# CZ201E_V2_0.net
KiCad netlist of a schematic drawn in Altium Designer
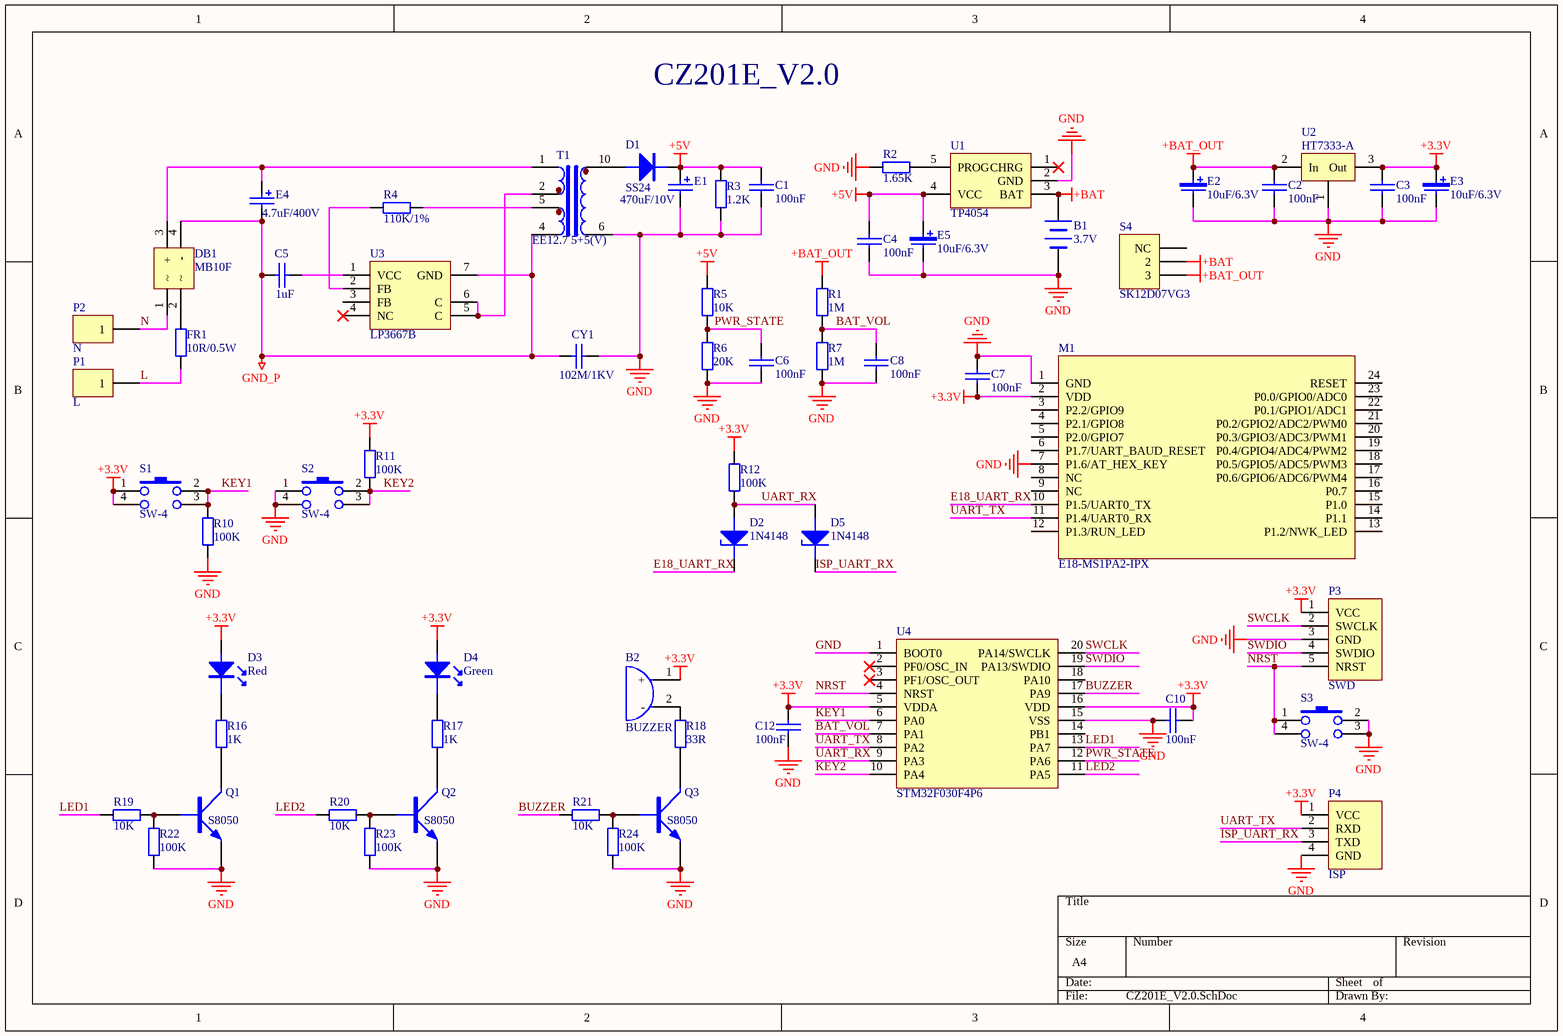
[diagram p0: CZ201E_V2.0.SchDoc]

(export (version "E")
  (design (tool "Eeschema 10.0.6"))
  (components
    (comp (ref "B1")
      (value "3.7V")
      (footprint "Cheng_Interface Unit:XH2.54-2P-BAT")
      (libsource (lib "Cheng_Misc Component") (part "BATTERY"))
    )
    (comp (ref "B2")
      (value "BUZZER")
      (footprint "Cheng_Misc Component:BEEZ")
      (libsource (lib "Cheng_Misc Component") (part "BUZZER"))
    )
    (comp (ref "C1")
      (value "100nF")
      (footprint "Cheng_Resistor_Capacitor:0603_CN")
      (libsource (lib "Cheng_Resistor_Capacitor") (part "Cap1"))
    )
    (comp (ref "C2")
      (value "100nF")
      (footprint "Cheng_Resistor_Capacitor:0603_CN")
      (libsource (lib "Cheng_Resistor_Capacitor") (part "Cap1"))
    )
    (comp (ref "C3")
      (value "100nF")
      (footprint "Cheng_Resistor_Capacitor:0603_CN")
      (libsource (lib "Cheng_Resistor_Capacitor") (part "Cap1"))
    )
    (comp (ref "C4")
      (value "100nF")
      (footprint "Cheng_Resistor_Capacitor:0603_CN")
      (libsource (lib "Cheng_Resistor_Capacitor") (part "Cap1"))
    )
    (comp (ref "C5")
      (value "1uF")
      (footprint "Cheng_Resistor_Capacitor:0603_CN")
      (libsource (lib "Cheng_Resistor_Capacitor") (part "Cap1"))
    )
    (comp (ref "C6")
      (value "100nF")
      (footprint "Cheng_Resistor_Capacitor:0603_CN")
      (libsource (lib "Cheng_Resistor_Capacitor") (part "Cap1"))
    )
    (comp (ref "C7")
      (value "100nF")
      (footprint "Cheng_Resistor_Capacitor:0603_CN")
      (libsource (lib "Cheng_Resistor_Capacitor") (part "Cap1"))
    )
    (comp (ref "C8")
      (value "100nF")
      (footprint "Cheng_Resistor_Capacitor:0603_CN")
      (libsource (lib "Cheng_Resistor_Capacitor") (part "Cap1"))
    )
    (comp (ref "C10")
      (value "100nF")
      (footprint "Cheng_Resistor_Capacitor:0603_CN")
      (libsource (lib "Cheng_Resistor_Capacitor") (part "Cap1"))
    )
    (comp (ref "C12")
      (value "100nF")
      (footprint "Cheng_Resistor_Capacitor:0603_CN")
      (libsource (lib "Cheng_Resistor_Capacitor") (part "Cap1"))
    )
    (comp (ref "CY1")
      (value "102M/1KV")
      (footprint "Cheng_Resistor_Capacitor:CY-5MM")
      (libsource (lib "Cheng_Resistor_Capacitor") (part "Cap1"))
    )
    (comp (ref "D1")
      (value "SS24")
      (footprint "Cheng_Diode_Transistor:DO-214AC(SMA)")
      (description "SS14,SS24,SS34,M7")
      (libsource (lib "Cheng_Diode_Transistor") (part "Diode-A"))
    )
    (comp (ref "D2")
      (value "1N4148")
      (footprint "Cheng_Diode_Transistor:LL-34")
      (libsource (lib "Cheng_Diode_Transistor") (part "Diode-B"))
    )
    (comp (ref "D3")
      (value "Red")
      (footprint "Cheng_Diode_Transistor:0603_LED")
      (libsource (lib "Cheng_Diode_Transistor") (part "LED"))
    )
    (comp (ref "D4")
      (value "Green")
      (footprint "Cheng_Diode_Transistor:0603_LED")
      (libsource (lib "Cheng_Diode_Transistor") (part "LED"))
    )
    (comp (ref "D5")
      (value "1N4148")
      (footprint "Cheng_Diode_Transistor:LL-34")
      (libsource (lib "Cheng_Diode_Transistor") (part "Diode-B"))
    )
    (comp (ref "DB1")
      (value "MB10F")
      (footprint "Cheng_Diode_Transistor:MB10F")
      (libsource (lib "Cheng_Diode_Transistor") (part "MB10F"))
    )
    (comp (ref "E1")
      (value "470uF/10V")
      (footprint "Cheng_Resistor_Capacitor:CS_470uF/16V")
      (libsource (lib "Cheng_Resistor_Capacitor") (part "Cap Pol1"))
    )
    (comp (ref "E2")
      (value "10uF/6.3V")
      (footprint "Cheng_Resistor_Capacitor:3216_E")
      (libsource (lib "Cheng_Resistor_Capacitor") (part "Cap Ta"))
    )
    (comp (ref "E3")
      (value "10uF/6.3V")
      (footprint "Cheng_Resistor_Capacitor:3216_E")
      (libsource (lib "Cheng_Resistor_Capacitor") (part "Cap Ta"))
    )
    (comp (ref "E4")
      (value "4.7uF/400V")
      (footprint "Cheng_Resistor_Capacitor:CS_220uF/25V")
      (libsource (lib "Cheng_Resistor_Capacitor") (part "Cap Pol1"))
    )
    (comp (ref "E5")
      (value "10uF/6.3V")
      (footprint "Cheng_Resistor_Capacitor:3216_E")
      (libsource (lib "Cheng_Resistor_Capacitor") (part "Cap Ta"))
    )
    (comp (ref "FR1")
      (value "10R/0.5W")
      (footprint "Cheng_Resistor_Capacitor:R0.12L")
      (libsource (lib "") (part "Res1_1"))
    )
    (comp (ref "M1")
      (value "E18-MS1PA2-IPX")
      (footprint "Cheng_Module:E18-MS1PA2-IPX")
      (libsource (lib "Cheng_Module") (part "E18-MS1PA2-IPX"))
    )
    (comp (ref "P1")
      (value "L")
      (footprint "Cheng_Interface Unit:CP3M-6*5*8.5MM")
      (description "Header, 1-Pin")
      (fields (field (name "PUBLISHER") "Altium Limited"))
      (libsource (lib "Cheng_Interface Unit") (part "Header 1"))
    )
    (comp (ref "P2")
      (value "N")
      (footprint "Cheng_Interface Unit:CP3M-6*5*8.5MM")
      (description "Header, 1-Pin")
      (fields (field (name "PUBLISHER") "Altium Limited"))
      (libsource (lib "Cheng_Interface Unit") (part "Header 1"))
    )
    (comp (ref "P3")
      (value "SWD")
      (footprint "Cheng_Interface Unit:XH2.54-5P")
      (libsource (lib "Cheng_Interface Unit") (part "SWD"))
    )
    (comp (ref "P4")
      (value "ISP")
      (footprint "Cheng_Interface Unit:XH2.54-4P")
      (libsource (lib "Cheng_Interface Unit") (part "ISP_UART"))
    )
    (comp (ref "Q1")
      (value "S8050")
      (footprint "Cheng_Diode_Transistor:SOT-23")
      (libsource (lib "Cheng_Diode_Transistor") (part "8050"))
    )
    (comp (ref "Q2")
      (value "S8050")
      (footprint "Cheng_Diode_Transistor:SOT-23")
      (libsource (lib "Cheng_Diode_Transistor") (part "8050"))
    )
    (comp (ref "Q3")
      (value "S8050")
      (footprint "Cheng_Diode_Transistor:SOT-23")
      (libsource (lib "Cheng_Diode_Transistor") (part "8050"))
    )
    (comp (ref "R1")
      (value "1M")
      (footprint "Cheng_Resistor_Capacitor:0603_RN")
      (libsource (lib "") (part "Res1_1"))
    )
    (comp (ref "R2")
      (value "1.65K")
      (footprint "Cheng_Resistor_Capacitor:0603_RN")
      (libsource (lib "") (part "Res1_2"))
    )
    (comp (ref "R3")
      (value "1.2K")
      (footprint "Cheng_Resistor_Capacitor:0603_RN")
      (libsource (lib "") (part "Res1_1"))
    )
    (comp (ref "R4")
      (value "110K/1%")
      (footprint "Cheng_Resistor_Capacitor:0603_RN")
      (libsource (lib "") (part "Res1_2"))
    )
    (comp (ref "R5")
      (value "10K")
      (footprint "Cheng_Resistor_Capacitor:0603_RN")
      (libsource (lib "") (part "Res1_1"))
    )
    (comp (ref "R6")
      (value "20K")
      (footprint "Cheng_Resistor_Capacitor:0603_RN")
      (libsource (lib "") (part "Res1_1"))
    )
    (comp (ref "R7")
      (value "1M")
      (footprint "Cheng_Resistor_Capacitor:0603_RN")
      (libsource (lib "") (part "Res1_1"))
    )
    (comp (ref "R10")
      (value "100K")
      (footprint "Cheng_Resistor_Capacitor:0603_RN")
      (libsource (lib "") (part "Res1_1"))
    )
    (comp (ref "R11")
      (value "100K")
      (footprint "Cheng_Resistor_Capacitor:0603_RN")
      (libsource (lib "") (part "Res1_1"))
    )
    (comp (ref "R12")
      (value "100K")
      (footprint "Cheng_Resistor_Capacitor:0603_RN")
      (libsource (lib "") (part "Res1_1"))
    )
    (comp (ref "R16")
      (value "1K")
      (footprint "Cheng_Resistor_Capacitor:0603_RN")
      (libsource (lib "") (part "Res1_1"))
    )
    (comp (ref "R17")
      (value "1K")
      (footprint "Cheng_Resistor_Capacitor:0603_RN")
      (libsource (lib "") (part "Res1_1"))
    )
    (comp (ref "R18")
      (value "33R")
      (footprint "Cheng_Resistor_Capacitor:0603_RN")
      (libsource (lib "") (part "Res1_1"))
    )
    (comp (ref "R19")
      (value "10K")
      (footprint "Cheng_Resistor_Capacitor:0603_RN")
      (libsource (lib "Cheng_Resistor_Capacitor") (part "Res1"))
    )
    (comp (ref "R20")
      (value "10K")
      (footprint "Cheng_Resistor_Capacitor:0603_RN")
      (libsource (lib "Cheng_Resistor_Capacitor") (part "Res1"))
    )
    (comp (ref "R21")
      (value "10K")
      (footprint "Cheng_Resistor_Capacitor:0603_RN")
      (libsource (lib "Cheng_Resistor_Capacitor") (part "Res1"))
    )
    (comp (ref "R22")
      (value "100K")
      (footprint "Cheng_Resistor_Capacitor:0603_RN")
      (libsource (lib "") (part "Res1_1"))
    )
    (comp (ref "R23")
      (value "100K")
      (footprint "Cheng_Resistor_Capacitor:0603_RN")
      (libsource (lib "") (part "Res1_1"))
    )
    (comp (ref "R24")
      (value "100K")
      (footprint "Cheng_Resistor_Capacitor:0603_RN")
      (libsource (lib "") (part "Res1_1"))
    )
    (comp (ref "S1")
      (value "SW-4")
      (footprint "Cheng_Misc Component:KEY-6*6MM-DIP")
      (libsource (lib "Cheng_Misc Component") (part "SW-4"))
    )
    (comp (ref "S2")
      (value "SW-4")
      (footprint "Cheng_Misc Component:KEY-6*6MM-DIP")
      (libsource (lib "Cheng_Misc Component") (part "SW-4"))
    )
    (comp (ref "S3")
      (value "SW-4")
      (footprint "Cheng_Misc Component:KEY-4*4*1.5MM-SMD")
      (libsource (lib "Cheng_Misc Component") (part "SW-4"))
    )
    (comp (ref "S4")
      (value "SK12D07VG3")
      (footprint "Cheng_Misc Component:SK12D07VG3")
      (libsource (lib "Cheng_Misc Component") (part "SK12D07VG3"))
    )
    (comp (ref "T1")
      (value "EE12.7 5+5(V)")
      (footprint "EE12.7 5+5(V)")
      (libsource (lib "CZ201E_V2.0") (part "EE12.7 5+5(V)"))
    )
    (comp (ref "U1")
      (value "TP4054")
      (footprint "Cheng_Diode_Transistor:SOT-23-5")
      (description "TP4054,LTC4054 ,PJ4054MR")
      (libsource (lib "Cheng_IC") (part "QX4054"))
    )
    (comp (ref "U2")
      (value "HT7333-A")
      (footprint "SOT-89")
      (description "HT7533; Output 500mA; Iq: 5uA, max= 7uA")
      (libsource (lib "Cheng_Manostat") (part "HT7833"))
    )
    (comp (ref "U3")
      (value "LP3667B")
      (footprint "Cheng_Manostat:SOP7")
      (description "LP3667A, LP3667B, LP3667AH, LP3667BH")
      (libsource (lib "Cheng_Manostat") (part "LP3667B"))
    )
    (comp (ref "U4")
      (value "STM32F030F4P6")
      (footprint "Cheng_IC:TSSOP20")
      (libsource (lib "Cheng_STM32") (part "STM32F030F4P6"))
    )
  )
  (nets
    (net (code "1") (name "+3.3V") (class "Default")
      (node (ref "B2") (pin "1") (pinfunction "+_1") (pintype "passive"))
      (node (ref "C10") (pin "1") (pinfunction "1_1") (pintype "passive"))
      (node (ref "C12") (pin "1") (pinfunction "1_1") (pintype "passive"))
      (node (ref "C3") (pin "1") (pinfunction "1_1") (pintype "passive"))
      (node (ref "C7") (pin "2") (pinfunction "2_2") (pintype "passive"))
      (node (ref "D3") (pin "A") (pinfunction "1_A") (pintype "passive"))
      (node (ref "D4") (pin "A") (pinfunction "1_A") (pintype "passive"))
      (node (ref "E3") (pin "1") (pinfunction "1_1") (pintype "passive"))
      (node (ref "M1") (pin "2") (pinfunction "VDD_2") (pintype "passive"))
      (node (ref "P3") (pin "1") (pinfunction "VCC_1") (pintype "passive"))
      (node (ref "P4") (pin "1") (pinfunction "VCC_1") (pintype "passive"))
      (node (ref "R11") (pin "2") (pinfunction "2_2") (pintype "passive"))
      (node (ref "R12") (pin "2") (pinfunction "2_2") (pintype "passive"))
      (node (ref "S1") (pin "1") (pinfunction "1_1") (pintype "passive"))
      (node (ref "S1") (pin "4") (pinfunction "4_4") (pintype "passive"))
      (node (ref "U2") (pin "3") (pinfunction "Out_3") (pintype "passive"))
      (node (ref "U4") (pin "16") (pinfunction "VDD_16") (pintype "passive"))
      (node (ref "U4") (pin "5") (pinfunction "VDDA_5") (pintype "passive"))
    )
    (net (code "2") (name "+5V") (class "Default")
      (node (ref "C1") (pin "1") (pinfunction "1_1") (pintype "passive"))
      (node (ref "C4") (pin "1") (pinfunction "1_1") (pintype "passive"))
      (node (ref "D1") (pin "K") (pinfunction "2_K") (pintype "passive"))
      (node (ref "E1") (pin "1") (pinfunction "1_1") (pintype "passive"))
      (node (ref "E5") (pin "1") (pinfunction "1_1") (pintype "passive"))
      (node (ref "R3") (pin "2") (pinfunction "2_2") (pintype "passive"))
      (node (ref "R5") (pin "2") (pinfunction "2_2") (pintype "passive"))
      (node (ref "U1") (pin "4") (pinfunction "VCC_4") (pintype "power_in"))
    )
    (net (code "3") (name "+BAT") (class "Default")
      (node (ref "B1") (pin "1") (pinfunction "+_1") (pintype "passive"))
      (node (ref "S4") (pin "2") (pinfunction "2_2") (pintype "passive"))
      (node (ref "U1") (pin "3") (pinfunction "BAT_3") (pintype "passive"))
    )
    (net (code "4") (name "+BAT_OUT") (class "Default")
      (node (ref "C2") (pin "1") (pinfunction "1_1") (pintype "passive"))
      (node (ref "E2") (pin "1") (pinfunction "1_1") (pintype "passive"))
      (node (ref "R1") (pin "2") (pinfunction "2_2") (pintype "passive"))
      (node (ref "S4") (pin "3") (pinfunction "3_3") (pintype "passive"))
      (node (ref "U2") (pin "2") (pinfunction "In_2") (pintype "passive"))
    )
    (net (code "5") (name "/BAT_VOL") (class "Default")
      (node (ref "C8") (pin "1") (pinfunction "1_1") (pintype "passive"))
      (node (ref "R1") (pin "1") (pinfunction "1_1") (pintype "passive"))
      (node (ref "R7") (pin "2") (pinfunction "2_2") (pintype "passive"))
      (node (ref "U4") (pin "7") (pinfunction "PA1_7") (pintype "passive"))
    )
    (net (code "6") (name "/BUZZER") (class "Default")
      (node (ref "R21") (pin "2") (pinfunction "2_2") (pintype "passive"))
      (node (ref "U4") (pin "17") (pinfunction "PA9_17") (pintype "passive"))
    )
    (net (code "7") (name "/E18_UART_RX") (class "Default")
      (node (ref "D2") (pin "K") (pinfunction "2_K") (pintype "passive"))
      (node (ref "M1") (pin "10") (pinfunction "P1.5/UART0_TX_10") (pintype "passive"))
    )
    (net (code "8") (name "/ISP_UART_RX") (class "Default")
      (node (ref "D5") (pin "K") (pinfunction "2_K") (pintype "passive"))
      (node (ref "P4") (pin "3") (pinfunction "TXD_3") (pintype "passive"))
    )
    (net (code "9") (name "/KEY1") (class "Default")
      (node (ref "R10") (pin "2") (pinfunction "2_2") (pintype "passive"))
      (node (ref "S1") (pin "2") (pinfunction "2_2") (pintype "passive"))
      (node (ref "S1") (pin "3") (pinfunction "3_3") (pintype "passive"))
      (node (ref "U4") (pin "6") (pinfunction "PA0_6") (pintype "passive"))
    )
    (net (code "10") (name "/KEY2") (class "Default")
      (node (ref "R11") (pin "1") (pinfunction "1_1") (pintype "passive"))
      (node (ref "S2") (pin "2") (pinfunction "2_2") (pintype "passive"))
      (node (ref "S2") (pin "3") (pinfunction "3_3") (pintype "passive"))
      (node (ref "U4") (pin "10") (pinfunction "PA4_10") (pintype "passive"))
    )
    (net (code "11") (name "/L") (class "Default")
      (node (ref "FR1") (pin "1") (pinfunction "1_1") (pintype "passive"))
      (node (ref "P1") (pin "1") (pinfunction "1_1") (pintype "passive"))
    )
    (net (code "12") (name "/LED1") (class "Default")
      (node (ref "R19") (pin "2") (pinfunction "2_2") (pintype "passive"))
      (node (ref "U4") (pin "13") (pinfunction "PA7_13") (pintype "passive"))
    )
    (net (code "13") (name "/LED2") (class "Default")
      (node (ref "R20") (pin "2") (pinfunction "2_2") (pintype "passive"))
      (node (ref "U4") (pin "11") (pinfunction "PA5_11") (pintype "passive"))
    )
    (net (code "14") (name "/N") (class "Default")
      (node (ref "DB1") (pin "1") (pinfunction "~_1") (pintype "passive"))
      (node (ref "P2") (pin "1") (pinfunction "1_1") (pintype "passive"))
    )
    (net (code "15") (name "/NRST") (class "Default")
      (node (ref "P3") (pin "5") (pinfunction "NRST_5") (pintype "passive"))
      (node (ref "S3") (pin "1") (pinfunction "1_1") (pintype "passive"))
      (node (ref "S3") (pin "4") (pinfunction "4_4") (pintype "passive"))
      (node (ref "U4") (pin "4") (pinfunction "NRST_4") (pintype "passive"))
    )
    (net (code "16") (name "/PWR_STATE") (class "Default")
      (node (ref "C6") (pin "1") (pinfunction "1_1") (pintype "passive"))
      (node (ref "R5") (pin "1") (pinfunction "1_1") (pintype "passive"))
      (node (ref "R6") (pin "2") (pinfunction "2_2") (pintype "passive"))
      (node (ref "U4") (pin "12") (pinfunction "PA6_12") (pintype "passive"))
    )
    (net (code "17") (name "/SWCLK") (class "Default")
      (node (ref "P3") (pin "2") (pinfunction "SWCLK_2") (pintype "passive"))
      (node (ref "U4") (pin "20") (pinfunction "PA14/SWCLK_20") (pintype "passive"))
    )
    (net (code "18") (name "/SWDIO") (class "Default")
      (node (ref "P3") (pin "4") (pinfunction "SWDIO_4") (pintype "passive"))
      (node (ref "U4") (pin "19") (pinfunction "PA13/SWDIO_19") (pintype "passive"))
    )
    (net (code "19") (name "/UART_RX") (class "Default")
      (node (ref "D2") (pin "A") (pinfunction "1_A") (pintype "passive"))
      (node (ref "D5") (pin "A") (pinfunction "1_A") (pintype "passive"))
      (node (ref "R12") (pin "1") (pinfunction "1_1") (pintype "passive"))
      (node (ref "U4") (pin "9") (pinfunction "PA3_9") (pintype "passive"))
    )
    (net (code "20") (name "/UART_TX") (class "Default")
      (node (ref "M1") (pin "11") (pinfunction "P1.4/UART0_RX_11") (pintype "passive"))
      (node (ref "P4") (pin "2") (pinfunction "RXD_2") (pintype "passive"))
      (node (ref "U4") (pin "8") (pinfunction "PA2_8") (pintype "passive"))
    )
    (net (code "21") (name "GND") (class "Default")
      (node (ref "B1") (pin "2") (pinfunction "-_2") (pintype "passive"))
      (node (ref "C1") (pin "2") (pinfunction "2_2") (pintype "passive"))
      (node (ref "C10") (pin "2") (pinfunction "2_2") (pintype "passive"))
      (node (ref "C12") (pin "2") (pinfunction "2_2") (pintype "passive"))
      (node (ref "C2") (pin "2") (pinfunction "2_2") (pintype "passive"))
      (node (ref "C3") (pin "2") (pinfunction "2_2") (pintype "passive"))
      (node (ref "C4") (pin "2") (pinfunction "2_2") (pintype "passive"))
      (node (ref "C6") (pin "2") (pinfunction "2_2") (pintype "passive"))
      (node (ref "C7") (pin "1") (pinfunction "1_1") (pintype "passive"))
      (node (ref "C8") (pin "2") (pinfunction "2_2") (pintype "passive"))
      (node (ref "CY1") (pin "2") (pinfunction "2_2") (pintype "passive"))
      (node (ref "E1") (pin "2") (pinfunction "2_2") (pintype "passive"))
      (node (ref "E2") (pin "2") (pinfunction "2_2") (pintype "passive"))
      (node (ref "E3") (pin "2") (pinfunction "2_2") (pintype "passive"))
      (node (ref "E5") (pin "2") (pinfunction "2_2") (pintype "passive"))
      (node (ref "M1") (pin "1") (pinfunction "GND_1") (pintype "passive"))
      (node (ref "M1") (pin "7") (pinfunction "P1.6/AT_HEX_KEY_7") (pintype "passive"))
      (node (ref "P3") (pin "3") (pinfunction "GND_3") (pintype "passive"))
      (node (ref "P4") (pin "4") (pinfunction "GND_4") (pintype "passive"))
      (node (ref "Q1") (pin "2") (pinfunction "E_2") (pintype "passive"))
      (node (ref "Q2") (pin "2") (pinfunction "E_2") (pintype "passive"))
      (node (ref "Q3") (pin "2") (pinfunction "E_2") (pintype "passive"))
      (node (ref "R10") (pin "1") (pinfunction "1_1") (pintype "passive"))
      (node (ref "R2") (pin "1") (pinfunction "1_1") (pintype "passive"))
      (node (ref "R22") (pin "1") (pinfunction "1_1") (pintype "passive"))
      (node (ref "R23") (pin "1") (pinfunction "1_1") (pintype "passive"))
      (node (ref "R24") (pin "1") (pinfunction "1_1") (pintype "passive"))
      (node (ref "R3") (pin "1") (pinfunction "1_1") (pintype "passive"))
      (node (ref "R6") (pin "1") (pinfunction "1_1") (pintype "passive"))
      (node (ref "R7") (pin "1") (pinfunction "1_1") (pintype "passive"))
      (node (ref "S2") (pin "1") (pinfunction "1_1") (pintype "passive"))
      (node (ref "S2") (pin "4") (pinfunction "4_4") (pintype "passive"))
      (node (ref "S3") (pin "2") (pinfunction "2_2") (pintype "passive"))
      (node (ref "S3") (pin "3") (pinfunction "3_3") (pintype "passive"))
      (node (ref "T1") (pin "6") (pinfunction "Ns_6") (pintype "passive"))
      (node (ref "U1") (pin "2") (pinfunction "GND_2") (pintype "passive"))
      (node (ref "U2") (pin "1") (pinfunction "GND_1") (pintype "passive"))
      (node (ref "U4") (pin "1") (pinfunction "BOOT0_1") (pintype "passive"))
      (node (ref "U4") (pin "15") (pinfunction "VSS_15") (pintype "passive"))
    )
    (net (code "22") (name "GND_P") (class "Default")
      (node (ref "C5") (pin "2") (pinfunction "2_2") (pintype "passive"))
      (node (ref "CY1") (pin "1") (pinfunction "1_1") (pintype "passive"))
      (node (ref "DB1") (pin "4") (pinfunction "-_4") (pintype "passive"))
      (node (ref "E4") (pin "2") (pinfunction "2_2") (pintype "passive"))
      (node (ref "T1") (pin "4") (pinfunction "Nd_4") (pintype "passive"))
      (node (ref "U3") (pin "7") (pinfunction "GND_7") (pintype "passive"))
    )
    (net (code "23") (name "Net-(B2--)") (class "Default")
      (node (ref "B2") (pin "2") (pinfunction "-_2") (pintype "passive"))
      (node (ref "R18") (pin "2") (pinfunction "2_2") (pintype "passive"))
    )
    (net (code "24") (name "Net-(D1-1)") (class "Default")
      (node (ref "D1") (pin "A") (pinfunction "1_A") (pintype "passive"))
      (node (ref "T1") (pin "10") (pinfunction "Ns_10") (pintype "passive"))
    )
    (net (code "25") (name "Net-(D3-2)") (class "Default")
      (node (ref "D3") (pin "K") (pinfunction "2_K") (pintype "passive"))
      (node (ref "R16") (pin "2") (pinfunction "2_2") (pintype "passive"))
    )
    (net (code "26") (name "Net-(D4-2)") (class "Default")
      (node (ref "D4") (pin "K") (pinfunction "2_K") (pintype "passive"))
      (node (ref "R17") (pin "2") (pinfunction "2_2") (pintype "passive"))
    )
    (net (code "27") (name "Net-(DB1-+)") (class "Default")
      (node (ref "DB1") (pin "3") (pinfunction "+_3") (pintype "passive"))
      (node (ref "E4") (pin "1") (pinfunction "1_1") (pintype "passive"))
      (node (ref "T1") (pin "1") (pinfunction "Np_1") (pintype "passive"))
    )
    (net (code "28") (name "Net-(DB1-~-Pad2)") (class "Default")
      (node (ref "DB1") (pin "2") (pinfunction "~_2") (pintype "passive"))
      (node (ref "FR1") (pin "2") (pinfunction "2_2") (pintype "passive"))
    )
    (net (code "29") (name "Net-(Q1-B)") (class "Default")
      (node (ref "Q1") (pin "1") (pinfunction "B_1") (pintype "passive"))
      (node (ref "R19") (pin "1") (pinfunction "1_1") (pintype "passive"))
      (node (ref "R22") (pin "2") (pinfunction "2_2") (pintype "passive"))
    )
    (net (code "30") (name "Net-(Q1-C)") (class "Default")
      (node (ref "Q1") (pin "3") (pinfunction "C_3") (pintype "passive"))
      (node (ref "R16") (pin "1") (pinfunction "1_1") (pintype "passive"))
    )
    (net (code "31") (name "Net-(Q2-B)") (class "Default")
      (node (ref "Q2") (pin "1") (pinfunction "B_1") (pintype "passive"))
      (node (ref "R20") (pin "1") (pinfunction "1_1") (pintype "passive"))
      (node (ref "R23") (pin "2") (pinfunction "2_2") (pintype "passive"))
    )
    (net (code "32") (name "Net-(Q2-C)") (class "Default")
      (node (ref "Q2") (pin "3") (pinfunction "C_3") (pintype "passive"))
      (node (ref "R17") (pin "1") (pinfunction "1_1") (pintype "passive"))
    )
    (net (code "33") (name "Net-(Q3-B)") (class "Default")
      (node (ref "Q3") (pin "1") (pinfunction "B_1") (pintype "passive"))
      (node (ref "R21") (pin "1") (pinfunction "1_1") (pintype "passive"))
      (node (ref "R24") (pin "2") (pinfunction "2_2") (pintype "passive"))
    )
    (net (code "34") (name "Net-(Q3-C)") (class "Default")
      (node (ref "Q3") (pin "3") (pinfunction "C_3") (pintype "passive"))
      (node (ref "R18") (pin "1") (pinfunction "1_1") (pintype "passive"))
    )
    (net (code "35") (name "Net-(R4-Pad1)") (class "Default")
      (node (ref "R4") (pin "1") (pinfunction "1_1") (pintype "passive"))
      (node (ref "U3") (pin "2") (pinfunction "FB_2") (pintype "passive"))
    )
    (net (code "36") (name "Net-(R4-Pad2)") (class "Default")
      (node (ref "R4") (pin "2") (pinfunction "2_2") (pintype "passive"))
      (node (ref "T1") (pin "5") (pinfunction "Nd_5") (pintype "passive"))
    )
    (net (code "37") (name "Net-(T1-Np-Pad2)") (class "Default")
      (node (ref "T1") (pin "2") (pinfunction "Np_2") (pintype "passive"))
      (node (ref "U3") (pin "5") (pinfunction "C_5") (pintype "passive"))
      (node (ref "U3") (pin "6") (pinfunction "C_6") (pintype "passive"))
    )
    (net (code "38") (name "Net-(U1-PROG)") (class "Default")
      (node (ref "R2") (pin "2") (pinfunction "2_2") (pintype "passive"))
      (node (ref "U1") (pin "5") (pinfunction "PROG_5") (pintype "passive"))
    )
    (net (code "39") (name "Net-(U3-VCC)") (class "Default")
      (node (ref "C5") (pin "1") (pinfunction "1_1") (pintype "passive"))
      (node (ref "U3") (pin "1") (pinfunction "VCC_1") (pintype "passive"))
    )
    (net (code "40") (name "unconnected-(M1-NC-Pad8)") (class "Default")
      (node (ref "M1") (pin "8") (pinfunction "NC_8") (pintype "passive"))
    )
    (net (code "41") (name "unconnected-(M1-NC-Pad9)") (class "Default")
      (node (ref "M1") (pin "9") (pinfunction "NC_9") (pintype "passive"))
    )
    (net (code "42") (name "unconnected-(M1-P0.0{slash}GPIO0{slash}ADC0-Pad23)") (class "Default")
      (node (ref "M1") (pin "23") (pinfunction "P0.0/GPIO0/ADC0_23") (pintype "passive"))
    )
    (net (code "43") (name "unconnected-(M1-P0.1{slash}GPIO1{slash}ADC1-Pad22)") (class "Default")
      (node (ref "M1") (pin "22") (pinfunction "P0.1/GPIO1/ADC1_22") (pintype "passive"))
    )
    (net (code "44") (name "unconnected-(M1-P0.2{slash}GPIO2{slash}ADC2{slash}PWM0-Pad21)") (class "Default")
      (node (ref "M1") (pin "21") (pinfunction "P0.2/GPIO2/ADC2/PWM0_21") (pintype "passive"))
    )
    (net (code "45") (name "unconnected-(M1-P0.3{slash}GPIO3{slash}ADC3{slash}PWM1-Pad20)") (class "Default")
      (node (ref "M1") (pin "20") (pinfunction "P0.3/GPIO3/ADC3/PWM1_20") (pintype "passive"))
    )
    (net (code "46") (name "unconnected-(M1-P0.4{slash}GPIO4{slash}ADC4{slash}PWM2-Pad19)") (class "Default")
      (node (ref "M1") (pin "19") (pinfunction "P0.4/GPIO4/ADC4/PWM2_19") (pintype "passive"))
    )
    (net (code "47") (name "unconnected-(M1-P0.5{slash}GPIO5{slash}ADC5{slash}PWM3-Pad18)") (class "Default")
      (node (ref "M1") (pin "18") (pinfunction "P0.5/GPIO5/ADC5/PWM3_18") (pintype "passive"))
    )
    (net (code "48") (name "unconnected-(M1-P0.6{slash}GPIO6{slash}ADC6{slash}PWM4-Pad17)") (class "Default")
      (node (ref "M1") (pin "17") (pinfunction "P0.6/GPIO6/ADC6/PWM4_17") (pintype "passive"))
    )
    (net (code "49") (name "unconnected-(M1-P0.7-Pad16)") (class "Default")
      (node (ref "M1") (pin "16") (pinfunction "P0.7_16") (pintype "passive"))
    )
    (net (code "50") (name "unconnected-(M1-P1.0-Pad15)") (class "Default")
      (node (ref "M1") (pin "15") (pinfunction "P1.0_15") (pintype "passive"))
    )
    (net (code "51") (name "unconnected-(M1-P1.1-Pad14)") (class "Default")
      (node (ref "M1") (pin "14") (pinfunction "P1.1_14") (pintype "passive"))
    )
    (net (code "52") (name "unconnected-(M1-P1.2{slash}NWK_LED-Pad13)") (class "Default")
      (node (ref "M1") (pin "13") (pinfunction "P1.2/NWK_LED_13") (pintype "passive"))
    )
    (net (code "53") (name "unconnected-(M1-P1.3{slash}RUN_LED-Pad12)") (class "Default")
      (node (ref "M1") (pin "12") (pinfunction "P1.3/RUN_LED_12") (pintype "passive"))
    )
    (net (code "54") (name "unconnected-(M1-P1.7{slash}UART_BAUD_RESET-Pad6)") (class "Default")
      (node (ref "M1") (pin "6") (pinfunction "P1.7/UART_BAUD_RESET_6") (pintype "passive"))
    )
    (net (code "55") (name "unconnected-(M1-P2.0{slash}GPIO7-Pad5)") (class "Default")
      (node (ref "M1") (pin "5") (pinfunction "P2.0/GPIO7_5") (pintype "passive"))
    )
    (net (code "56") (name "unconnected-(M1-P2.1{slash}GPIO8-Pad4)") (class "Default")
      (node (ref "M1") (pin "4") (pinfunction "P2.1/GPIO8_4") (pintype "passive"))
    )
    (net (code "57") (name "unconnected-(M1-P2.2{slash}GPIO9-Pad3)") (class "Default")
      (node (ref "M1") (pin "3") (pinfunction "P2.2/GPIO9_3") (pintype "passive"))
    )
    (net (code "58") (name "unconnected-(M1-RESET-Pad24)") (class "Default")
      (node (ref "M1") (pin "24") (pinfunction "RESET_24") (pintype "passive"))
    )
    (net (code "59") (name "unconnected-(S4-NC-Pad1)") (class "Default")
      (node (ref "S4") (pin "1") (pinfunction "NC_1") (pintype "passive"))
    )
    (net (code "60") (name "unconnected-(U1-CHRG-Pad1)") (class "Default")
      (node (ref "U1") (pin "1") (pinfunction "CHRG_1") (pintype "passive+no_connect"))
    )
    (net (code "61") (name "unconnected-(U3-FB-Pad3)") (class "Default")
      (node (ref "U3") (pin "3") (pinfunction "FB_3") (pintype "passive"))
    )
    (net (code "62") (name "unconnected-(U3-NC-Pad4)") (class "Default")
      (node (ref "U3") (pin "4") (pinfunction "NC_4") (pintype "passive+no_connect"))
    )
    (net (code "63") (name "unconnected-(U4-PA10-Pad18)") (class "Default")
      (node (ref "U4") (pin "18") (pinfunction "PA10_18") (pintype "passive"))
    )
    (net (code "64") (name "unconnected-(U4-PB1-Pad14)") (class "Default")
      (node (ref "U4") (pin "14") (pinfunction "PB1_14") (pintype "passive"))
    )
    (net (code "65") (name "unconnected-(U4-PF0{slash}OSC_IN-Pad2)") (class "Default")
      (node (ref "U4") (pin "2") (pinfunction "PF0/OSC_IN_2") (pintype "passive+no_connect"))
    )
    (net (code "66") (name "unconnected-(U4-PF1{slash}OSC_OUT-Pad3)") (class "Default")
      (node (ref "U4") (pin "3") (pinfunction "PF1/OSC_OUT_3") (pintype "passive+no_connect"))
    )
  )
)
